# Alimentation.net
KiCad netlist of a schematic drawn in EAGLE
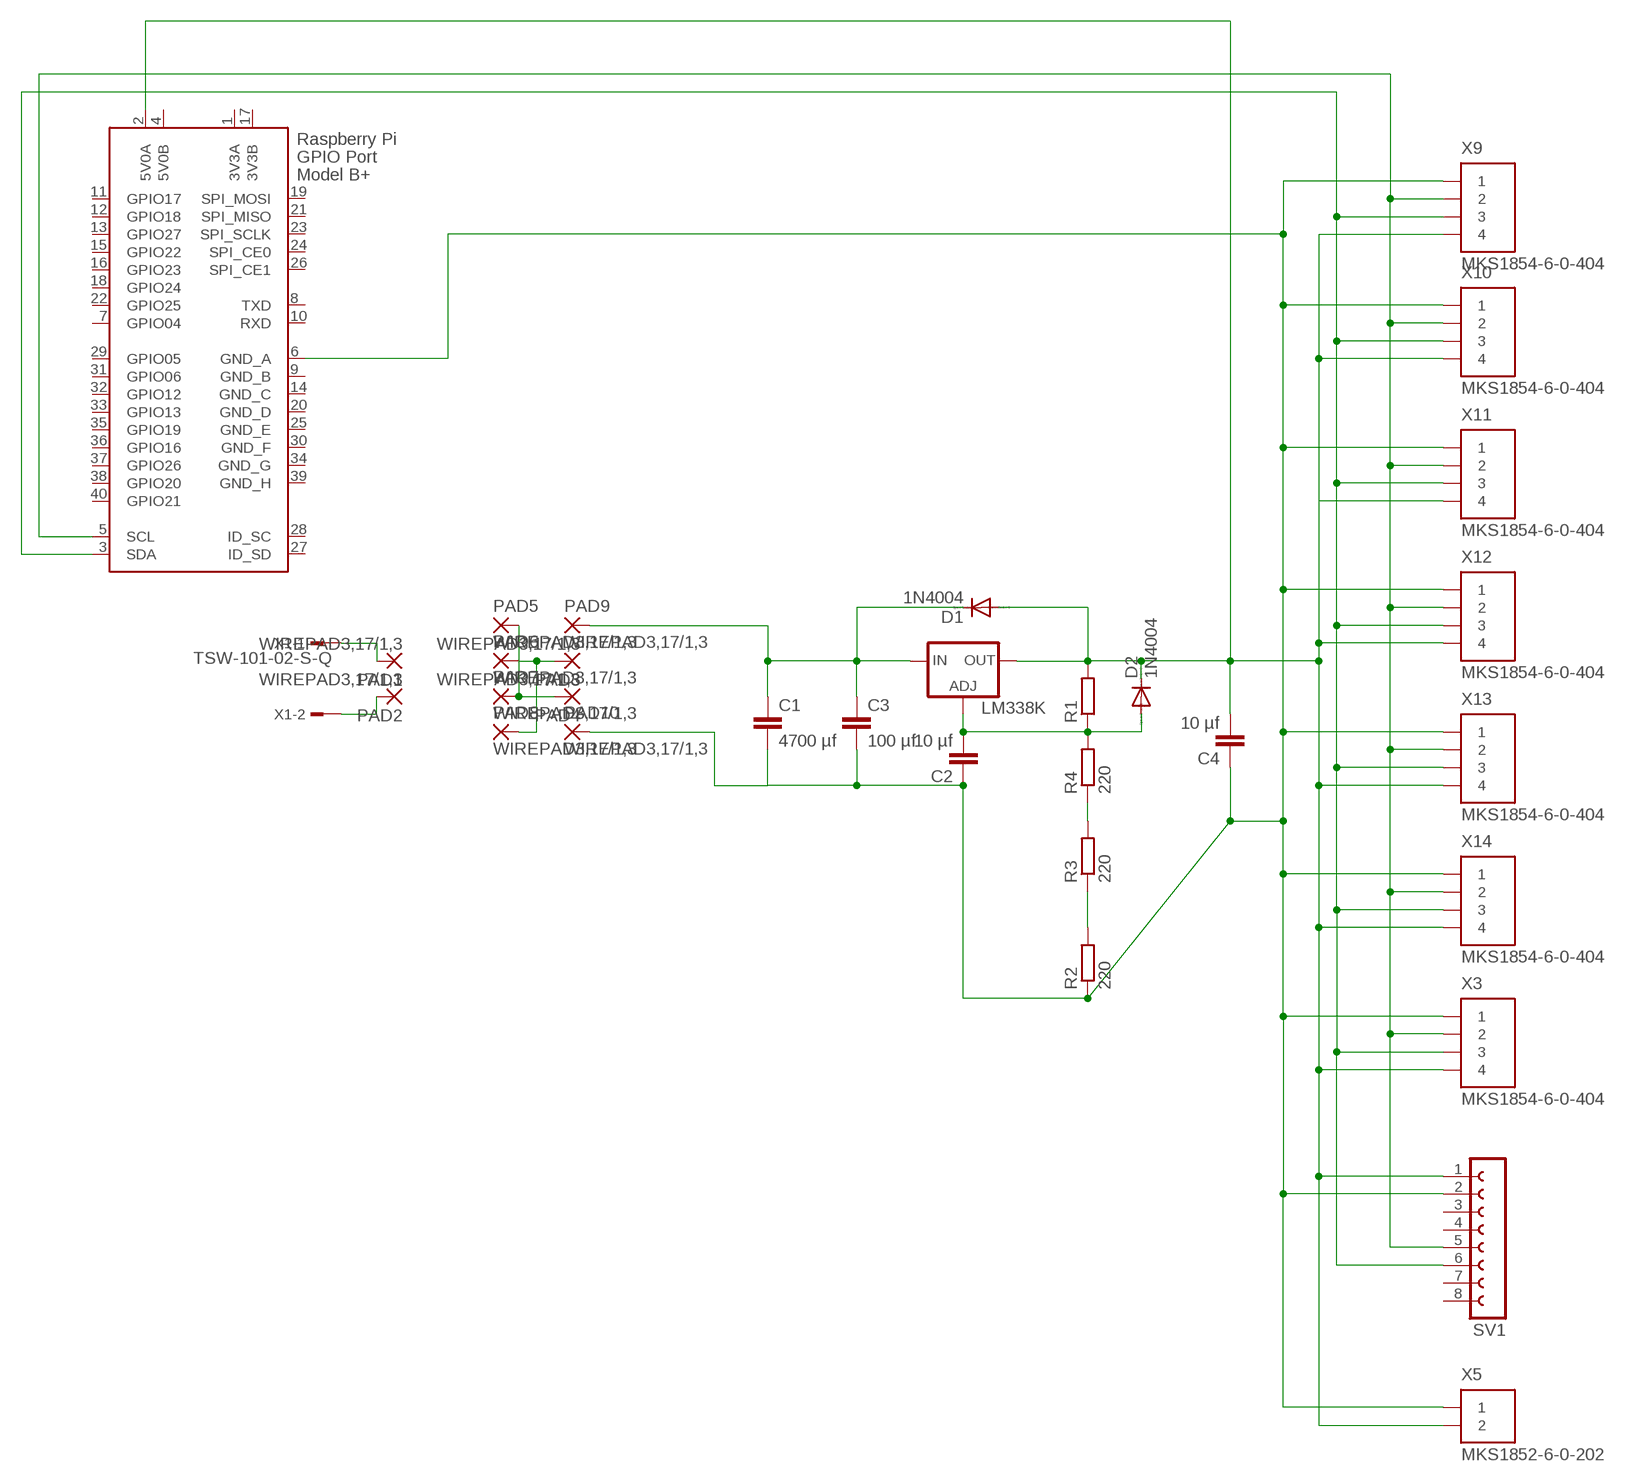
[diagram p0: schematic, sheet 1]

(export (version "E")
  (design (tool "Eeschema 10.0.6"))
  (components
    (comp (ref "C1")
      (value "4700 µf")
      (footprint "eagle-import:C075-032X103")
      (libsource (lib "eagle-import") (part "C-EU075-032X103"))
    )
    (comp (ref "C2")
      (value "10 µf")
      (footprint "eagle-import:C22.5B6")
      (libsource (lib "eagle-import") (part "C22/6"))
    )
    (comp (ref "C3")
      (value "100 µf")
      (footprint "eagle-import:C050-075X075")
      (libsource (lib "eagle-import") (part "C-EU050-075X075"))
    )
    (comp (ref "C4")
      (value "10 µf")
      (footprint "eagle-import:C22.5B6")
      (libsource (lib "eagle-import") (part "C22/6"))
    )
    (comp (ref "D1")
      (value "1N4004")
      (footprint "eagle-import:DO41-10")
      (libsource (lib "eagle-import") (part "1N4004"))
    )
    (comp (ref "D2")
      (value "1N4004")
      (footprint "eagle-import:DO41-10")
      (libsource (lib "eagle-import") (part "1N4004"))
    )
    (comp (ref "LM338K")
      (value "LM317-TO3")
      (footprint "eagle-import:TO3-K02")
      (libsource (lib "eagle-import") (part "LM317-TO3"))
    )
    (comp (ref "PAD1")
      (value "WIREPAD3,17/1,3")
      (footprint "eagle-import:3,17_1,3")
      (libsource (lib "eagle-import") (part "WIREPAD3,17/1,3"))
    )
    (comp (ref "PAD2")
      (value "WIREPAD3,17/1,3")
      (footprint "eagle-import:3,17_1,3")
      (libsource (lib "eagle-import") (part "WIREPAD3,17/1,3"))
    )
    (comp (ref "PAD3")
      (value "WIREPAD3,17/1,3")
      (footprint "eagle-import:3,17_1,3")
      (libsource (lib "eagle-import") (part "WIREPAD3,17/1,3"))
    )
    (comp (ref "PAD4")
      (value "WIREPAD3,17/1,3")
      (footprint "eagle-import:3,17_1,3")
      (libsource (lib "eagle-import") (part "WIREPAD3,17/1,3"))
    )
    (comp (ref "PAD5")
      (value "WIREPAD3,17/1,3")
      (footprint "eagle-import:3,17_1,3")
      (libsource (lib "eagle-import") (part "WIREPAD3,17/1,3"))
    )
    (comp (ref "PAD6")
      (value "WIREPAD3,17/1,3")
      (footprint "eagle-import:3,17_1,3")
      (libsource (lib "eagle-import") (part "WIREPAD3,17/1,3"))
    )
    (comp (ref "PAD7")
      (value "WIREPAD3,17/1,3")
      (footprint "eagle-import:3,17_1,3")
      (libsource (lib "eagle-import") (part "WIREPAD3,17/1,3"))
    )
    (comp (ref "PAD8")
      (value "WIREPAD3,17/1,3")
      (footprint "eagle-import:3,17_1,3")
      (libsource (lib "eagle-import") (part "WIREPAD3,17/1,3"))
    )
    (comp (ref "PAD9")
      (value "WIREPAD3,17/1,3")
      (footprint "eagle-import:3,17_1,3")
      (libsource (lib "eagle-import") (part "WIREPAD3,17/1,3"))
    )
    (comp (ref "PAD10")
      (value "WIREPAD3,17/1,3")
      (footprint "eagle-import:3,17_1,3")
      (libsource (lib "eagle-import") (part "WIREPAD3,17/1,3"))
    )
    (comp (ref "R1")
      (value "R-EU_0309/12")
      (footprint "eagle-import:0309_12")
      (libsource (lib "eagle-import") (part "R-EU_0309/12"))
    )
    (comp (ref "R2")
      (value "220")
      (footprint "eagle-import:0309_12")
      (libsource (lib "eagle-import") (part "R-EU_0309/12"))
    )
    (comp (ref "R3")
      (value "220")
      (footprint "eagle-import:0309_12")
      (libsource (lib "eagle-import") (part "R-EU_0309/12"))
    )
    (comp (ref "R4")
      (value "220")
      (footprint "eagle-import:0309_12")
      (libsource (lib "eagle-import") (part "R-EU_0309/12"))
    )
    (comp (ref "SV1")
      (value "FE08-1")
      (footprint "eagle-import:FE08")
      (libsource (lib "eagle-import") (part "FE08-1"))
    )
    (comp (ref "X1")
      (value "TSW-101-02-S-Q")
      (footprint "eagle-import:TSW-101-02-S-Q")
      (libsource (lib "eagle-import") (part "TSW-101-02-S-Q"))
    )
    (comp (ref "X2")
      (value "RASPI_GPIO_B+#_PIN")
      (footprint "eagle-import:RASPI_GPIO_B+_PIN")
      (libsource (lib "eagle-import") (part "RASPI_GPIO_B+#_PIN"))
    )
    (comp (ref "X3")
      (value "MKS1854-6-0-404")
      (footprint "eagle-import:MKS1854-6-0-404")
      (libsource (lib "eagle-import") (part "MKS1854-6-0-404"))
    )
    (comp (ref "X5")
      (value "MKS1852-6-0-202")
      (footprint "eagle-import:MKS1852-6-0-202")
      (libsource (lib "eagle-import") (part "MKS1852-6-0-202"))
    )
    (comp (ref "X9")
      (value "MKS1854-6-0-404")
      (footprint "eagle-import:MKS1854-6-0-404")
      (libsource (lib "eagle-import") (part "MKS1854-6-0-404"))
    )
    (comp (ref "X10")
      (value "MKS1854-6-0-404")
      (footprint "eagle-import:MKS1854-6-0-404")
      (libsource (lib "eagle-import") (part "MKS1854-6-0-404"))
    )
    (comp (ref "X11")
      (value "MKS1854-6-0-404")
      (footprint "eagle-import:MKS1854-6-0-404")
      (libsource (lib "eagle-import") (part "MKS1854-6-0-404"))
    )
    (comp (ref "X12")
      (value "MKS1854-6-0-404")
      (footprint "eagle-import:MKS1854-6-0-404")
      (libsource (lib "eagle-import") (part "MKS1854-6-0-404"))
    )
    (comp (ref "X13")
      (value "MKS1854-6-0-404")
      (footprint "eagle-import:MKS1854-6-0-404")
      (libsource (lib "eagle-import") (part "MKS1854-6-0-404"))
    )
    (comp (ref "X14")
      (value "MKS1854-6-0-404")
      (footprint "eagle-import:MKS1854-6-0-404")
      (libsource (lib "eagle-import") (part "MKS1854-6-0-404"))
    )
  )
  (nets
    (net (code "1") (name "/3V3A") (class "Default")
      (node (ref "X2") (pin "1") (pinfunction "3V3A_1") (pintype "power_in"))
    )
    (net (code "2") (name "/3V3B") (class "Default")
      (node (ref "X2") (pin "17") (pinfunction "3V3B_17") (pintype "power_in"))
    )
    (net (code "3") (name "/5V0B") (class "Default")
      (node (ref "X2") (pin "4") (pinfunction "5V0B_4") (pintype "power_in"))
    )
    (net (code "4") (name "/GND_B") (class "Default")
      (node (ref "X2") (pin "9") (pinfunction "GND_B_9") (pintype "power_in"))
    )
    (net (code "5") (name "/GND_C") (class "Default")
      (node (ref "X2") (pin "14") (pinfunction "GND_C_14") (pintype "power_in"))
    )
    (net (code "6") (name "/GND_D") (class "Default")
      (node (ref "X2") (pin "20") (pinfunction "GND_D_20") (pintype "power_in"))
    )
    (net (code "7") (name "/GND_E") (class "Default")
      (node (ref "X2") (pin "25") (pinfunction "GND_E_25") (pintype "power_in"))
    )
    (net (code "8") (name "/GND_F") (class "Default")
      (node (ref "X2") (pin "30") (pinfunction "GND_F_30") (pintype "power_in"))
    )
    (net (code "9") (name "/GND_G") (class "Default")
      (node (ref "X2") (pin "34") (pinfunction "GND_G_34") (pintype "power_in"))
    )
    (net (code "10") (name "/GND_H") (class "Default")
      (node (ref "X2") (pin "39") (pinfunction "GND_H_39") (pintype "power_in"))
    )
    (net (code "11") (name "Net-(LM338K-ADJ)") (class "Default")
      (node (ref "C2") (pin "2") (pinfunction "2_2") (pintype "passive"))
      (node (ref "D2") (pin "A") (pinfunction "A_A") (pintype "passive"))
      (node (ref "LM338K") (pin "2") (pinfunction "ADJ_2") (pintype "input"))
      (node (ref "R1") (pin "1") (pinfunction "1_1") (pintype "passive"))
      (node (ref "R4") (pin "2") (pinfunction "2_2") (pintype "passive"))
    )
    (net (code "12") (name "Net-(LM338K-IN)") (class "Default")
      (node (ref "C1") (pin "1") (pinfunction "1_1") (pintype "passive"))
      (node (ref "C3") (pin "1") (pinfunction "1_1") (pintype "passive"))
      (node (ref "D1") (pin "C") (pinfunction "C_C") (pintype "passive"))
      (node (ref "LM338K") (pin "1") (pinfunction "IN_1") (pintype "input"))
      (node (ref "PAD9") (pin "1") (pinfunction "P_1") (pintype "passive"))
    )
    (net (code "13") (name "Net-(LM338K-OUT)") (class "Default")
      (node (ref "C4") (pin "2") (pinfunction "2_2") (pintype "passive"))
      (node (ref "D1") (pin "A") (pinfunction "A_A") (pintype "passive"))
      (node (ref "D2") (pin "C") (pinfunction "C_C") (pintype "passive"))
      (node (ref "LM338K") (pin "3") (pinfunction "OUT_3") (pintype "passive"))
      (node (ref "R1") (pin "2") (pinfunction "2_2") (pintype "passive"))
      (node (ref "SV1") (pin "1") (pinfunction "1_1") (pintype "passive"))
      (node (ref "X10") (pin "4") (pinfunction "4_4") (pintype "input"))
      (node (ref "X11") (pin "4") (pinfunction "4_4") (pintype "input"))
      (node (ref "X12") (pin "4") (pinfunction "4_4") (pintype "input"))
      (node (ref "X13") (pin "4") (pinfunction "4_4") (pintype "input"))
      (node (ref "X14") (pin "4") (pinfunction "4_4") (pintype "input"))
      (node (ref "X2") (pin "2") (pinfunction "5V0A_2") (pintype "power_in"))
      (node (ref "X3") (pin "4") (pinfunction "4_4") (pintype "input"))
      (node (ref "X5") (pin "2") (pinfunction "2_2") (pintype "input"))
      (node (ref "X9") (pin "4") (pinfunction "4_4") (pintype "input"))
    )
    (net (code "14") (name "Net-(PAD1-P)") (class "Default")
      (node (ref "PAD1") (pin "1") (pinfunction "P_1") (pintype "passive"))
      (node (ref "X1") (pin "1") (pinfunction "1_1") (pintype "passive"))
    )
    (net (code "15") (name "Net-(PAD2-P)") (class "Default")
      (node (ref "PAD2") (pin "1") (pinfunction "P_1") (pintype "passive"))
      (node (ref "X1") (pin "2") (pinfunction "1_2") (pintype "passive"))
    )
    (net (code "16") (name "Net-(PAD3-P)") (class "Default")
      (node (ref "PAD3") (pin "1") (pinfunction "P_1") (pintype "passive"))
      (node (ref "PAD6") (pin "1") (pinfunction "P_1") (pintype "passive"))
      (node (ref "PAD8") (pin "1") (pinfunction "P_1") (pintype "passive"))
    )
    (net (code "17") (name "Net-(PAD4-P)") (class "Default")
      (node (ref "PAD4") (pin "1") (pinfunction "P_1") (pintype "passive"))
      (node (ref "PAD5") (pin "1") (pinfunction "P_1") (pintype "passive"))
      (node (ref "PAD7") (pin "1") (pinfunction "P_1") (pintype "passive"))
    )
    (net (code "18") (name "Net-(PAD10-P)") (class "Default")
      (node (ref "C1") (pin "2") (pinfunction "2_2") (pintype "passive"))
      (node (ref "C2") (pin "1") (pinfunction "1_1") (pintype "passive"))
      (node (ref "C3") (pin "2") (pinfunction "2_2") (pintype "passive"))
      (node (ref "C4") (pin "1") (pinfunction "1_1") (pintype "passive"))
      (node (ref "PAD10") (pin "1") (pinfunction "P_1") (pintype "passive"))
      (node (ref "R2") (pin "1") (pinfunction "1_1") (pintype "passive"))
      (node (ref "SV1") (pin "2") (pinfunction "2_2") (pintype "passive"))
      (node (ref "X10") (pin "1") (pinfunction "1_1") (pintype "input"))
      (node (ref "X11") (pin "1") (pinfunction "1_1") (pintype "input"))
      (node (ref "X12") (pin "1") (pinfunction "1_1") (pintype "input"))
      (node (ref "X13") (pin "1") (pinfunction "1_1") (pintype "input"))
      (node (ref "X14") (pin "1") (pinfunction "1_1") (pintype "input"))
      (node (ref "X2") (pin "6") (pinfunction "GND_A_6") (pintype "power_in"))
      (node (ref "X3") (pin "1") (pinfunction "1_1") (pintype "input"))
      (node (ref "X5") (pin "1") (pinfunction "1_1") (pintype "input"))
      (node (ref "X9") (pin "1") (pinfunction "1_1") (pintype "input"))
    )
    (net (code "19") (name "Net-(R2-Pad2)") (class "Default")
      (node (ref "R2") (pin "2") (pinfunction "2_2") (pintype "passive"))
      (node (ref "R3") (pin "1") (pinfunction "1_1") (pintype "passive"))
    )
    (net (code "20") (name "Net-(R3-Pad2)") (class "Default")
      (node (ref "R3") (pin "2") (pinfunction "2_2") (pintype "passive"))
      (node (ref "R4") (pin "1") (pinfunction "1_1") (pintype "passive"))
    )
    (net (code "21") (name "Net-(X2-SCL)") (class "Default")
      (node (ref "SV1") (pin "5") (pinfunction "5_5") (pintype "passive"))
      (node (ref "X10") (pin "2") (pinfunction "2_2") (pintype "input"))
      (node (ref "X11") (pin "2") (pinfunction "2_2") (pintype "input"))
      (node (ref "X12") (pin "2") (pinfunction "2_2") (pintype "input"))
      (node (ref "X13") (pin "2") (pinfunction "2_2") (pintype "input"))
      (node (ref "X14") (pin "2") (pinfunction "2_2") (pintype "input"))
      (node (ref "X2") (pin "5") (pinfunction "SCL_5") (pintype "bidirectional"))
      (node (ref "X3") (pin "2") (pinfunction "2_2") (pintype "input"))
      (node (ref "X9") (pin "2") (pinfunction "2_2") (pintype "input"))
    )
    (net (code "22") (name "Net-(X2-SDA)") (class "Default")
      (node (ref "SV1") (pin "6") (pinfunction "6_6") (pintype "passive"))
      (node (ref "X10") (pin "3") (pinfunction "3_3") (pintype "input"))
      (node (ref "X11") (pin "3") (pinfunction "3_3") (pintype "input"))
      (node (ref "X12") (pin "3") (pinfunction "3_3") (pintype "input"))
      (node (ref "X13") (pin "3") (pinfunction "3_3") (pintype "input"))
      (node (ref "X14") (pin "3") (pinfunction "3_3") (pintype "input"))
      (node (ref "X2") (pin "3") (pinfunction "SDA_3") (pintype "bidirectional"))
      (node (ref "X3") (pin "3") (pinfunction "3_3") (pintype "input"))
      (node (ref "X9") (pin "3") (pinfunction "3_3") (pintype "input"))
    )
    (net (code "23") (name "unconnected-(SV1-Pad3)") (class "Default")
      (node (ref "SV1") (pin "3") (pinfunction "3_3") (pintype "passive"))
    )
    (net (code "24") (name "unconnected-(SV1-Pad4)") (class "Default")
      (node (ref "SV1") (pin "4") (pinfunction "4_4") (pintype "passive"))
    )
    (net (code "25") (name "unconnected-(SV1-Pad7)") (class "Default")
      (node (ref "SV1") (pin "7") (pinfunction "7_7") (pintype "passive"))
    )
    (net (code "26") (name "unconnected-(SV1-Pad8)") (class "Default")
      (node (ref "SV1") (pin "8") (pinfunction "8_8") (pintype "passive"))
    )
    (net (code "27") (name "unconnected-(X2-GPIO04-Pad7)") (class "Default")
      (node (ref "X2") (pin "7") (pinfunction "GPIO04_7") (pintype "bidirectional"))
    )
    (net (code "28") (name "unconnected-(X2-GPIO05-Pad29)") (class "Default")
      (node (ref "X2") (pin "29") (pinfunction "GPIO05_29") (pintype "no_connect"))
    )
    (net (code "29") (name "unconnected-(X2-GPIO06-Pad31)") (class "Default")
      (node (ref "X2") (pin "31") (pinfunction "GPIO06_31") (pintype "no_connect"))
    )
    (net (code "30") (name "unconnected-(X2-GPIO12-Pad32)") (class "Default")
      (node (ref "X2") (pin "32") (pinfunction "GPIO12_32") (pintype "no_connect"))
    )
    (net (code "31") (name "unconnected-(X2-GPIO13-Pad33)") (class "Default")
      (node (ref "X2") (pin "33") (pinfunction "GPIO13_33") (pintype "no_connect"))
    )
    (net (code "32") (name "unconnected-(X2-GPIO16-Pad36)") (class "Default")
      (node (ref "X2") (pin "36") (pinfunction "GPIO16_36") (pintype "no_connect"))
    )
    (net (code "33") (name "unconnected-(X2-GPIO17-Pad11)") (class "Default")
      (node (ref "X2") (pin "11") (pinfunction "GPIO17_11") (pintype "bidirectional"))
    )
    (net (code "34") (name "unconnected-(X2-GPIO18-Pad12)") (class "Default")
      (node (ref "X2") (pin "12") (pinfunction "GPIO18_12") (pintype "bidirectional"))
    )
    (net (code "35") (name "unconnected-(X2-GPIO19-Pad35)") (class "Default")
      (node (ref "X2") (pin "35") (pinfunction "GPIO19_35") (pintype "no_connect"))
    )
    (net (code "36") (name "unconnected-(X2-GPIO20-Pad38)") (class "Default")
      (node (ref "X2") (pin "38") (pinfunction "GPIO20_38") (pintype "no_connect"))
    )
    (net (code "37") (name "unconnected-(X2-GPIO21-Pad40)") (class "Default")
      (node (ref "X2") (pin "40") (pinfunction "GPIO21_40") (pintype "no_connect"))
    )
    (net (code "38") (name "unconnected-(X2-GPIO22-Pad15)") (class "Default")
      (node (ref "X2") (pin "15") (pinfunction "GPIO22_15") (pintype "bidirectional"))
    )
    (net (code "39") (name "unconnected-(X2-GPIO23-Pad16)") (class "Default")
      (node (ref "X2") (pin "16") (pinfunction "GPIO23_16") (pintype "bidirectional"))
    )
    (net (code "40") (name "unconnected-(X2-GPIO24-Pad18)") (class "Default")
      (node (ref "X2") (pin "18") (pinfunction "GPIO24_18") (pintype "bidirectional"))
    )
    (net (code "41") (name "unconnected-(X2-GPIO25-Pad22)") (class "Default")
      (node (ref "X2") (pin "22") (pinfunction "GPIO25_22") (pintype "bidirectional"))
    )
    (net (code "42") (name "unconnected-(X2-GPIO26-Pad37)") (class "Default")
      (node (ref "X2") (pin "37") (pinfunction "GPIO26_37") (pintype "no_connect"))
    )
    (net (code "43") (name "unconnected-(X2-GPIO27-Pad13)") (class "Default")
      (node (ref "X2") (pin "13") (pinfunction "GPIO27_13") (pintype "bidirectional"))
    )
    (net (code "44") (name "unconnected-(X2-ID_SC-Pad28)") (class "Default")
      (node (ref "X2") (pin "28") (pinfunction "ID_SC_28") (pintype "no_connect"))
    )
    (net (code "45") (name "unconnected-(X2-ID_SD-Pad27)") (class "Default")
      (node (ref "X2") (pin "27") (pinfunction "ID_SD_27") (pintype "no_connect"))
    )
    (net (code "46") (name "unconnected-(X2-RXD-Pad10)") (class "Default")
      (node (ref "X2") (pin "10") (pinfunction "RXD_10") (pintype "bidirectional"))
    )
    (net (code "47") (name "unconnected-(X2-SPI_CE0-Pad24)") (class "Default")
      (node (ref "X2") (pin "24") (pinfunction "SPI_CE0_24") (pintype "bidirectional"))
    )
    (net (code "48") (name "unconnected-(X2-SPI_CE1-Pad26)") (class "Default")
      (node (ref "X2") (pin "26") (pinfunction "SPI_CE1_26") (pintype "bidirectional"))
    )
    (net (code "49") (name "unconnected-(X2-SPI_MISO-Pad21)") (class "Default")
      (node (ref "X2") (pin "21") (pinfunction "SPI_MISO_21") (pintype "bidirectional"))
    )
    (net (code "50") (name "unconnected-(X2-SPI_MOSI-Pad19)") (class "Default")
      (node (ref "X2") (pin "19") (pinfunction "SPI_MOSI_19") (pintype "bidirectional"))
    )
    (net (code "51") (name "unconnected-(X2-SPI_SCLK-Pad23)") (class "Default")
      (node (ref "X2") (pin "23") (pinfunction "SPI_SCLK_23") (pintype "bidirectional"))
    )
    (net (code "52") (name "unconnected-(X2-TXD-Pad8)") (class "Default")
      (node (ref "X2") (pin "8") (pinfunction "TXD_8") (pintype "bidirectional"))
    )
  )
)
